# Interface.net
KiCad netlist of a schematic drawn in Altium Designer
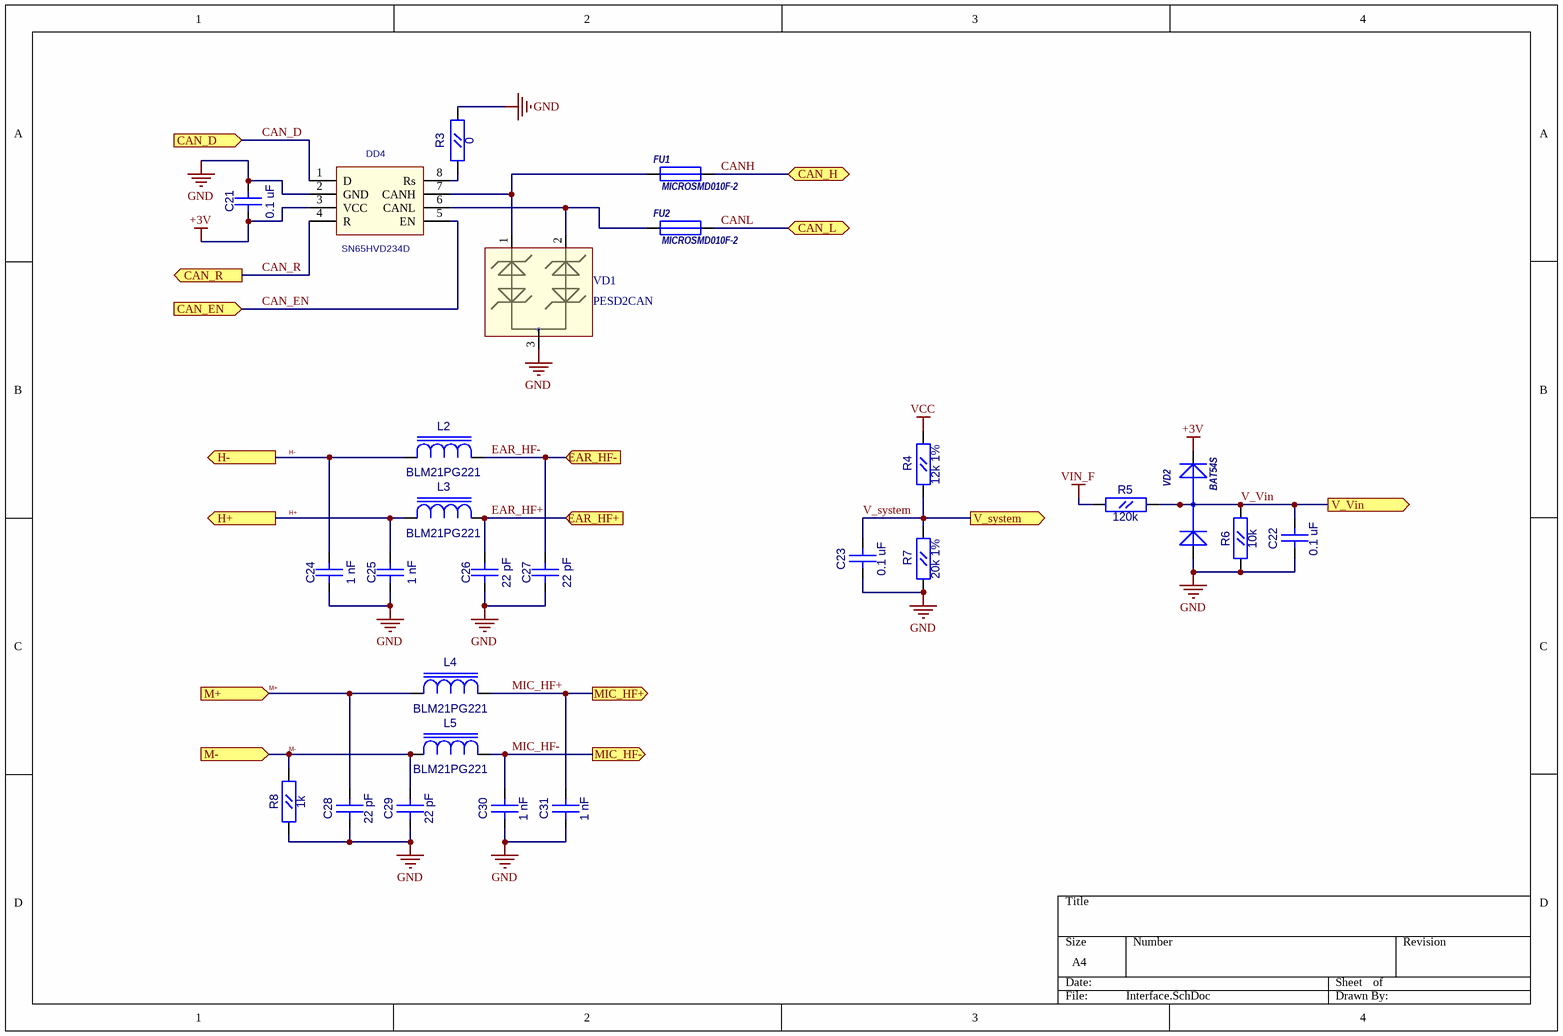
[diagram p0: Interface.SchDoc]

(export (version "E")
  (design (tool "Eeschema 10.0.6"))
  (components
    (comp (ref "C21")
      (value "0.1 uF")
      (footprint "CC0603")
      (description "CC0603")
      (libsource (lib "*") (part "CC0603"))
    )
    (comp (ref "C22")
      (value "0.1 uF")
      (footprint "CC0603")
      (description "CC0603")
      (libsource (lib "gprs_modem_2") (part "CC0603"))
    )
    (comp (ref "C23")
      (value "0.1 uF")
      (footprint "CC0603")
      (description "CC0603")
      (libsource (lib "gprs_modem_2") (part "CC0603"))
    )
    (comp (ref "C24")
      (value "1 nF")
      (footprint "CC0603")
      (description "CC0603")
      (libsource (lib "*") (part "CC0603"))
    )
    (comp (ref "C25")
      (value "1 nF")
      (footprint "CC0603")
      (description "CC0603")
      (libsource (lib "*") (part "CC0603"))
    )
    (comp (ref "C26")
      (value "22 pF")
      (footprint "CC0603")
      (description "CC0603")
      (libsource (lib "*") (part "CC0603"))
    )
    (comp (ref "C27")
      (value "22 pF")
      (footprint "CC0603")
      (description "CC0603")
      (libsource (lib "*") (part "CC0603"))
    )
    (comp (ref "C28")
      (value "22 pF")
      (footprint "CC0603")
      (description "CC0603")
      (libsource (lib "*") (part "CC0603"))
    )
    (comp (ref "C29")
      (value "22 pF")
      (footprint "CC0603")
      (description "CC0603")
      (libsource (lib "*") (part "CC0603"))
    )
    (comp (ref "C30")
      (value "1 nF")
      (footprint "CC0603")
      (description "CC0603")
      (libsource (lib "*") (part "CC0603"))
    )
    (comp (ref "C31")
      (value "1 nF")
      (footprint "CC0603")
      (description "CC0603")
      (libsource (lib "*") (part "CC0603"))
    )
    (comp (ref "DD4")
      (value "SN65HVD234D")
      (footprint "SO-8")
      (description "CAN Transceiver")
      (libsource (lib "gprs_modem") (part "SN65HVD234D"))
    )
    (comp (ref "FU1")
      (value "MICROSMD010F-2")
      (footprint "RC1210")
      (description "MICROSMD")
      (libsource (lib "gprs_modem_2") (part "MICROSMD"))
    )
    (comp (ref "FU2")
      (value "MICROSMD010F-2")
      (footprint "RC1210")
      (description "MICROSMD")
      (libsource (lib "gprs_modem_2") (part "MICROSMD"))
    )
    (comp (ref "L2") (value "BLM21PG221") (footprint "RC0805") (libsource (lib "*") (part "BLM21PG221")))
    (comp (ref "L3") (value "BLM21PG221") (footprint "RC0805") (libsource (lib "*") (part "BLM21PG221")))
    (comp (ref "L4") (value "BLM21PG221") (footprint "RC0805") (libsource (lib "") (part "BLM21PG221_1")))
    (comp (ref "L5") (value "BLM21PG221") (footprint "RC0805") (libsource (lib "") (part "BLM21PG221_1")))
    (comp (ref "R3")
      (value "0")
      (footprint "RC0603")
      (description "RC0603")
      (libsource (lib "*") (part "RC0603"))
    )
    (comp (ref "R4")
      (value "12k 1%")
      (footprint "RC0603")
      (description "RC0603")
      (libsource (lib "*") (part "RC0603"))
    )
    (comp (ref "R5")
      (value "120k")
      (footprint "RC0603")
      (description "RC0603")
      (libsource (lib "*") (part "RC0603"))
    )
    (comp (ref "R6")
      (value "10k")
      (footprint "RC0603")
      (description "RC0603")
      (libsource (lib "*") (part "RC0603"))
    )
    (comp (ref "R7")
      (value "20k 1%")
      (footprint "RC0603")
      (description "RC0603")
      (libsource (lib "*") (part "RC0603"))
    )
    (comp (ref "R8")
      (value "1k")
      (footprint "RC0603")
      (description "RC0603")
      (libsource (lib "*") (part "RC0603"))
    )
    (comp (ref "VD1")
      (value "PESD2CAN")
      (footprint "SOT-23(123)")
      (description "TVS for CAN")
      (libsource (lib "gprs_modem") (part "PESD2CAN"))
    )
    (comp (ref "VD2")
      (value "BAT54S")
      (footprint "SOT-23(GSD)")
      (description "1.0 Ampere General Purpose Rectifier")
      (libsource (lib "gprs_modem") (part "BAT54S"))
    )
  )
  (nets
    (net (code "1") (name "+3V") (class "Default")
      (node (ref "C21") (pin "1") (pinfunction "A_1") (pintype "passive"))
      (node (ref "DD4") (pin "3") (pinfunction "VCC_3") (pintype "passive"))
      (node (ref "VD2") (pin "2") (pinfunction "K_2") (pintype "passive"))
    )
    (net (code "2") (name "/CANH") (class "Default") (node (ref "FU1") (pin "2") (pintype "passive")))
    (net (code "3") (name "/CANL") (class "Default") (node (ref "FU2") (pin "2") (pintype "passive")))
    (net (code "4") (name "/CAN_D") (class "Default")
      (node (ref "DD4") (pin "1") (pinfunction "D_1") (pintype "passive"))
    )
    (net (code "5") (name "/CAN_EN") (class "Default")
      (node (ref "DD4") (pin "5") (pinfunction "EN_5") (pintype "passive"))
    )
    (net (code "6") (name "/CAN_R") (class "Default")
      (node (ref "DD4") (pin "4") (pinfunction "R_4") (pintype "passive"))
    )
    (net (code "7") (name "/EAR_HF+") (class "Default")
      (node (ref "C26") (pin "2") (pinfunction "B_2") (pintype "passive"))
      (node (ref "L3") (pin "1") (pinfunction "A_1") (pintype "passive"))
    )
    (net (code "8") (name "/EAR_HF-") (class "Default")
      (node (ref "C27") (pin "2") (pinfunction "B_2") (pintype "passive"))
      (node (ref "L2") (pin "1") (pinfunction "A_1") (pintype "passive"))
    )
    (net (code "9") (name "/H+") (class "Default")
      (node (ref "C25") (pin "2") (pinfunction "B_2") (pintype "passive"))
      (node (ref "L3") (pin "2") (pinfunction "B_2") (pintype "passive"))
    )
    (net (code "10") (name "/H-") (class "Default")
      (node (ref "C24") (pin "2") (pinfunction "B_2") (pintype "passive"))
      (node (ref "L2") (pin "2") (pinfunction "B_2") (pintype "passive"))
    )
    (net (code "11") (name "/M+") (class "Default")
      (node (ref "C28") (pin "2") (pinfunction "B_2") (pintype "passive"))
      (node (ref "L4") (pin "1") (pinfunction "A_1") (pintype "passive"))
    )
    (net (code "12") (name "/M-") (class "Default")
      (node (ref "C29") (pin "2") (pinfunction "B_2") (pintype "passive"))
      (node (ref "L5") (pin "1") (pinfunction "A_1") (pintype "passive"))
      (node (ref "R8") (pin "2") (pinfunction "B_2") (pintype "passive"))
    )
    (net (code "13") (name "/MIC_HF+") (class "Default")
      (node (ref "C31") (pin "2") (pinfunction "B_2") (pintype "passive"))
      (node (ref "L4") (pin "2") (pinfunction "B_2") (pintype "passive"))
    )
    (net (code "14") (name "/MIC_HF-") (class "Default")
      (node (ref "C30") (pin "2") (pinfunction "B_2") (pintype "passive"))
      (node (ref "L5") (pin "2") (pinfunction "B_2") (pintype "passive"))
    )
    (net (code "15") (name "/V_Vin") (class "Default")
      (node (ref "C22") (pin "1") (pinfunction "A_1") (pintype "passive"))
      (node (ref "R5") (pin "1") (pinfunction "A_1") (pintype "passive"))
      (node (ref "R6") (pin "1") (pinfunction "A_1") (pintype "passive"))
      (node (ref "VD2") (pin "3") (pinfunction "AK_3") (pintype "passive"))
    )
    (net (code "16") (name "/V_system") (class "Default")
      (node (ref "C23") (pin "1") (pinfunction "A_1") (pintype "passive"))
      (node (ref "R4") (pin "1") (pinfunction "A_1") (pintype "passive"))
      (node (ref "R7") (pin "2") (pinfunction "B_2") (pintype "passive"))
    )
    (net (code "17") (name "GND") (class "Default")
      (node (ref "C21") (pin "2") (pinfunction "B_2") (pintype "passive"))
      (node (ref "C22") (pin "2") (pinfunction "B_2") (pintype "passive"))
      (node (ref "C23") (pin "2") (pinfunction "B_2") (pintype "passive"))
      (node (ref "C24") (pin "1") (pinfunction "A_1") (pintype "passive"))
      (node (ref "C25") (pin "1") (pinfunction "A_1") (pintype "passive"))
      (node (ref "C26") (pin "1") (pinfunction "A_1") (pintype "passive"))
      (node (ref "C27") (pin "1") (pinfunction "A_1") (pintype "passive"))
      (node (ref "C28") (pin "1") (pinfunction "A_1") (pintype "passive"))
      (node (ref "C29") (pin "1") (pinfunction "A_1") (pintype "passive"))
      (node (ref "C30") (pin "1") (pinfunction "A_1") (pintype "passive"))
      (node (ref "C31") (pin "1") (pinfunction "A_1") (pintype "passive"))
      (node (ref "DD4") (pin "2") (pinfunction "GND_2") (pintype "passive"))
      (node (ref "R3") (pin "2") (pinfunction "B_2") (pintype "passive"))
      (node (ref "R6") (pin "2") (pinfunction "B_2") (pintype "passive"))
      (node (ref "R7") (pin "1") (pinfunction "A_1") (pintype "passive"))
      (node (ref "R8") (pin "1") (pinfunction "A_1") (pintype "passive"))
      (node (ref "VD1") (pin "3") (pinfunction "3_3") (pintype "passive"))
      (node (ref "VD2") (pin "1") (pinfunction "A_1") (pintype "passive"))
    )
    (net (code "18") (name "Net-(DD4-CANH)") (class "Default")
      (node (ref "DD4") (pin "7") (pinfunction "CANH_7") (pintype "passive"))
      (node (ref "FU1") (pin "1") (pintype "passive"))
      (node (ref "VD1") (pin "1") (pinfunction "1_1") (pintype "passive"))
    )
    (net (code "19") (name "Net-(DD4-CANL)") (class "Default")
      (node (ref "DD4") (pin "6") (pinfunction "CANL_6") (pintype "passive"))
      (node (ref "FU2") (pin "1") (pintype "passive"))
      (node (ref "VD1") (pin "2") (pinfunction "2_2") (pintype "passive"))
    )
    (net (code "20") (name "Net-(DD4-Rs)") (class "Default")
      (node (ref "DD4") (pin "8") (pinfunction "Rs_8") (pintype "passive"))
      (node (ref "R3") (pin "1") (pinfunction "A_1") (pintype "passive"))
    )
    (net (code "21") (name "VCC") (class "Default")
      (node (ref "R4") (pin "2") (pinfunction "B_2") (pintype "passive"))
    )
    (net (code "22") (name "VIN_F") (class "Default")
      (node (ref "R5") (pin "2") (pinfunction "B_2") (pintype "passive"))
    )
  )
)
